# CAN_Module.net
KiCad netlist of a schematic drawn in Altium Designer
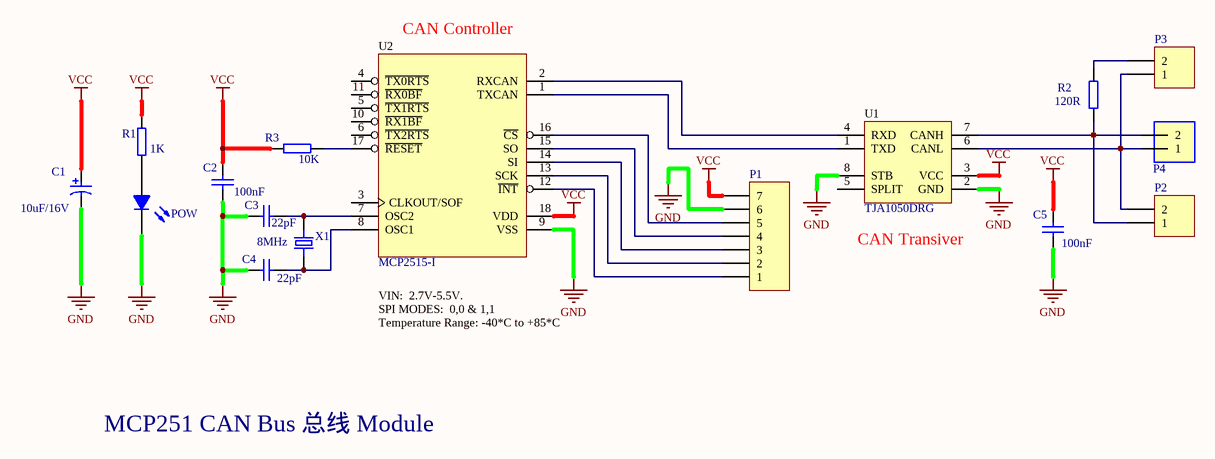
[diagram p0: CAN_Module.SchDoc]

(export (version "E")
  (design (tool "Eeschema 10.0.6"))
  (components
    (comp (ref "C1")
      (value "10uF/16V")
      (footprint "tantalum  A")
      (description "SMD Tantalum Capacitor")
      (libsource (lib "adafruit") (part "Cap_Tantalum"))
    )
    (comp (ref "C2")
      (value "100nF")
      (footprint "C0603")
      (description "Capacitor, X5R, ±10%, 6.3V")
      (fields
        (field (name "PART NUMBER") "C0603-N.C.")
        (field (name "MANUFACTURER") "N.A.")
        (field (name "PUBLISHER") "Nordic Semiconductor")
      )
      (libsource (lib "adafruit") (part "Cap_0603"))
    )
    (comp (ref "C3")
      (value "22pF")
      (footprint "C0603")
      (description "Capacitor, X5R, ±10%, 6.3V")
      (fields
        (field (name "PART NUMBER") "C0603-N.C.")
        (field (name "MANUFACTURER") "N.A.")
        (field (name "PUBLISHER") "Nordic Semiconductor")
      )
      (libsource (lib "adafruit") (part "Cap_0603"))
    )
    (comp (ref "C4")
      (value "22pF")
      (footprint "C0603")
      (description "Capacitor, X5R, ±10%, 6.3V")
      (fields
        (field (name "PART NUMBER") "C0603-N.C.")
        (field (name "MANUFACTURER") "N.A.")
        (field (name "PUBLISHER") "Nordic Semiconductor")
      )
      (libsource (lib "adafruit") (part "Cap_0603"))
    )
    (comp (ref "C5")
      (value "100nF")
      (footprint "C0603")
      (description "Capacitor, X5R, ±10%, 6.3V")
      (fields
        (field (name "PART NUMBER") "C0603-N.C.")
        (field (name "MANUFACTURER") "N.A.")
        (field (name "PUBLISHER") "Nordic Semiconductor")
      )
      (libsource (lib "adafruit") (part "Cap_0603"))
    )
    (comp (ref "P1")
      (value "Header 7")
      (footprint "HDR1X7")
      (description "Header, 7-Pin")
      (fields (field (name "PUBLISHER") "Altium Limited"))
      (libsource (lib "Miscellaneous Connectors") (part "Header 7"))
    )
    (comp (ref "P2")
      (value "Header 2")
      (footprint "HDR1X2")
      (description "Header, 2-Pin")
      (fields (field (name "PUBLISHER") "Altium Limited"))
      (libsource (lib "adafruit") (part "Header 2"))
    )
    (comp (ref "P3")
      (value "Header 2")
      (footprint "HDR1X2")
      (description "Header, 2-Pin")
      (fields (field (name "PUBLISHER") "Altium Limited"))
      (libsource (lib "adafruit") (part "Header 2"))
    )
    (comp (ref "P4")
      (value "Terminal Block 3.5mmPitch: 3,5 mmNumber of pins: 2Created by Rembrandt Electronicswww.rembrandtelectronics.com")
      (footprint "TERMINAL-BLOCK-2-PIN-3.5MM-ROUND-PAD")
      (description "Screw Terminal 3.5mm")
      (libsource (lib "adafruit") (part "TERMINAL-3.50-2P"))
    )
    (comp (ref "POW")
      (value "RED LED")
      (footprint "CHIPLED_0603")
      (description "SMD lamp beads")
      (libsource (lib "adafruit") (part "LEDCHIP-LED0603"))
    )
    (comp (ref "R1")
      (value "1kΩ")
      (footprint "R0603")
      (description "Resistor, ±1%, 0.100W")
      (fields
        (field (name "PART NUMBER") "R0603-N.C.Ω")
        (field (name "MANUFACTURER") "N.A.")
        (field (name "PUBLISHER") "Nordic Semiconductor")
      )
      (libsource (lib "adafruit") (part "Res_0603"))
    )
    (comp (ref "R2")
      (value "120Ω")
      (footprint "R0603")
      (description "Resistor, ±1%, 0.100W")
      (fields
        (field (name "PART NUMBER") "R0603-N.C.Ω")
        (field (name "MANUFACTURER") "N.A.")
        (field (name "PUBLISHER") "Nordic Semiconductor")
      )
      (libsource (lib "") (part "Res_0603_2"))
    )
    (comp (ref "R3")
      (value "10kΩ")
      (footprint "R0603")
      (description "Resistor, ±1%, 0.100W")
      (fields
        (field (name "PART NUMBER") "R0603-N.C.Ω")
        (field (name "MANUFACTURER") "N.A.")
        (field (name "PUBLISHER") "Nordic Semiconductor")
      )
      (libsource (lib "") (part "Res_0603_1"))
    )
    (comp (ref "U1")
      (value "TJA1050DRG")
      (footprint "SOIC-8E")
      (description "CAN Transiver")
      (fields (field (name "MANUFACTURER") "HGC(深圳汉芯)"))
      (libsource (lib "adafruit") (part "TJA1050DRG"))
    )
    (comp (ref "U2")
      (value "MCP2515-I")
      (footprint "SOIC-18_L11.6-W7.5-P1.27-LS10.3-BL")
      (description "CAN Controller")
      (fields (field (name "MANUFACTURER") "Tokmas(托克马斯)"))
      (libsource (lib "adafruit") (part "MCP2515"))
    )
    (comp (ref "X1")
      (value "8MHz")
      (footprint "HC-49US_L11.5-W4.5-P4.88")
      (description "10MHz Â±30ppm Crystal 20pF 60 Ohms HC-49/US")
      (fields (field (name "MP") "ECS-100-20-5PVX") (field (name "MF") "ECS Inc."))
      (libsource (lib "adafruit") (part "CRYSTAL-ECS-100-20-5PVX"))
    )
  )
  (nets
    (net (code "1") (name "GND") (class "Default")
      (node (ref "C1") (pin "2") (pinfunction "2_2") (pintype "passive"))
      (node (ref "C2") (pin "1") (pinfunction "1_1") (pintype "passive"))
      (node (ref "C3") (pin "2") (pinfunction "2_2") (pintype "passive"))
      (node (ref "C4") (pin "2") (pinfunction "2_2") (pintype "passive"))
      (node (ref "C5") (pin "1") (pinfunction "1_1") (pintype "passive"))
      (node (ref "P1") (pin "6") (pinfunction "6_6") (pintype "passive"))
      (node (ref "POW") (pin "C") (pinfunction "K_C") (pintype "passive"))
      (node (ref "U1") (pin "2") (pinfunction "GND_2") (pintype "passive"))
      (node (ref "U1") (pin "8") (pinfunction "STB_8") (pintype "passive"))
      (node (ref "U2") (pin "9") (pinfunction "VSS_9") (pintype "passive"))
    )
    (net (code "2") (name "Net-(P3-Pad2)") (class "Default")
      (node (ref "P3") (pin "2") (pinfunction "2_2") (pintype "passive"))
      (node (ref "R2") (pin "2") (pinfunction "2_2") (pintype "passive"))
    )
    (net (code "3") (name "Net-(POW-PadA)") (class "Default")
      (node (ref "POW") (pin "A") (pinfunction "A_A") (pintype "passive"))
      (node (ref "R1") (pin "2") (pinfunction "2_2") (pintype "passive"))
    )
    (net (code "4") (name "Net-(U1-CANH)") (class "Default")
      (node (ref "P2") (pin "1") (pinfunction "1_1") (pintype "passive"))
      (node (ref "P4") (pin "2") (pinfunction "2_2") (pintype "passive"))
      (node (ref "R2") (pin "1") (pinfunction "1_1") (pintype "passive"))
      (node (ref "U1") (pin "7") (pinfunction "CANH_7") (pintype "passive"))
    )
    (net (code "5") (name "Net-(U1-CANL)") (class "Default")
      (node (ref "P2") (pin "2") (pinfunction "2_2") (pintype "passive"))
      (node (ref "P3") (pin "1") (pinfunction "1_1") (pintype "passive"))
      (node (ref "P4") (pin "1") (pinfunction "1_1") (pintype "passive"))
      (node (ref "U1") (pin "6") (pinfunction "CANL_6") (pintype "passive"))
    )
    (net (code "6") (name "Net-(U1-RXD)") (class "Default")
      (node (ref "U1") (pin "4") (pinfunction "RXD_4") (pintype "passive"))
      (node (ref "U2") (pin "2") (pinfunction "RXCAN_2") (pintype "passive"))
    )
    (net (code "7") (name "Net-(U1-TXD)") (class "Default")
      (node (ref "U1") (pin "1") (pinfunction "TXD_1") (pintype "passive"))
      (node (ref "U2") (pin "1") (pinfunction "TXCAN_1") (pintype "passive"))
    )
    (net (code "8") (name "Net-(U2-OSC1)") (class "Default")
      (node (ref "C4") (pin "1") (pinfunction "1_1") (pintype "passive"))
      (node (ref "U2") (pin "8") (pinfunction "OSC1_8") (pintype "passive"))
      (node (ref "X1") (pin "1") (pinfunction "1_1") (pintype "passive"))
    )
    (net (code "9") (name "Net-(U2-OSC2)") (class "Default")
      (node (ref "C3") (pin "1") (pinfunction "1_1") (pintype "passive"))
      (node (ref "U2") (pin "7") (pinfunction "OSC2_7") (pintype "passive"))
      (node (ref "X1") (pin "2") (pinfunction "2_2") (pintype "passive"))
    )
    (net (code "10") (name "Net-(U2-SCK)") (class "Default")
      (node (ref "P1") (pin "2") (pinfunction "2_2") (pintype "passive"))
      (node (ref "U2") (pin "13") (pinfunction "SCK_13") (pintype "passive"))
    )
    (net (code "11") (name "Net-(U2-SI)") (class "Default")
      (node (ref "P1") (pin "3") (pinfunction "3_3") (pintype "passive"))
      (node (ref "U2") (pin "14") (pinfunction "SI_14") (pintype "passive"))
    )
    (net (code "12") (name "Net-(U2-SO)") (class "Default")
      (node (ref "P1") (pin "4") (pinfunction "4_4") (pintype "passive"))
      (node (ref "U2") (pin "15") (pinfunction "SO_15") (pintype "passive"))
    )
    (net (code "13") (name "Net-(U2-~{CS})") (class "Default")
      (node (ref "P1") (pin "5") (pinfunction "5_5") (pintype "passive"))
      (node (ref "U2") (pin "16") (pinfunction "~{CS}_16") (pintype "passive"))
    )
    (net (code "14") (name "Net-(U2-~{INT})") (class "Default")
      (node (ref "P1") (pin "1") (pinfunction "1_1") (pintype "passive"))
      (node (ref "U2") (pin "12") (pinfunction "~{INT}_12") (pintype "passive"))
    )
    (net (code "15") (name "Net-(U2-~{RESET})") (class "Default")
      (node (ref "R3") (pin "1") (pinfunction "1_1") (pintype "passive"))
      (node (ref "U2") (pin "17") (pinfunction "~{RESET}_17") (pintype "passive"))
    )
    (net (code "16") (name "VCC") (class "Default")
      (node (ref "C1") (pin "1") (pinfunction "1_1") (pintype "passive"))
      (node (ref "C2") (pin "2") (pinfunction "2_2") (pintype "passive"))
      (node (ref "C5") (pin "2") (pinfunction "2_2") (pintype "passive"))
      (node (ref "P1") (pin "7") (pinfunction "7_7") (pintype "passive"))
      (node (ref "R1") (pin "1") (pinfunction "1_1") (pintype "passive"))
      (node (ref "R3") (pin "2") (pinfunction "2_2") (pintype "passive"))
      (node (ref "U1") (pin "3") (pinfunction "VCC_3") (pintype "passive"))
      (node (ref "U2") (pin "18") (pinfunction "VDD_18") (pintype "passive"))
    )
    (net (code "17") (name "unconnected-(U1-SPLIT-Pad5)") (class "Default")
      (node (ref "U1") (pin "5") (pinfunction "SPLIT_5") (pintype "passive"))
    )
    (net (code "18") (name "unconnected-(U2-CLKOUT{slash}SOF-Pad3)") (class "Default")
      (node (ref "U2") (pin "3") (pinfunction "CLKOUT/SOF_3") (pintype "passive"))
    )
    (net (code "19") (name "unconnected-(U2-~{RX0BF}-Pad11)") (class "Default")
      (node (ref "U2") (pin "11") (pinfunction "~{RX0BF}_11") (pintype "passive"))
    )
    (net (code "20") (name "unconnected-(U2-~{RX1BF}-Pad10)") (class "Default")
      (node (ref "U2") (pin "10") (pinfunction "~{RX1BF}_10") (pintype "passive"))
    )
    (net (code "21") (name "unconnected-(U2-~{TX0RTS}-Pad4)") (class "Default")
      (node (ref "U2") (pin "4") (pinfunction "~{TX0RTS}_4") (pintype "passive"))
    )
    (net (code "22") (name "unconnected-(U2-~{TX1RTS}-Pad5)") (class "Default")
      (node (ref "U2") (pin "5") (pinfunction "~{TX1RTS}_5") (pintype "passive"))
    )
    (net (code "23") (name "unconnected-(U2-~{TX2RTS}-Pad6)") (class "Default")
      (node (ref "U2") (pin "6") (pinfunction "~{TX2RTS}_6") (pintype "passive"))
    )
  )
)
